# AL17150.net
KiCad netlist of a schematic drawn in Altium Designer
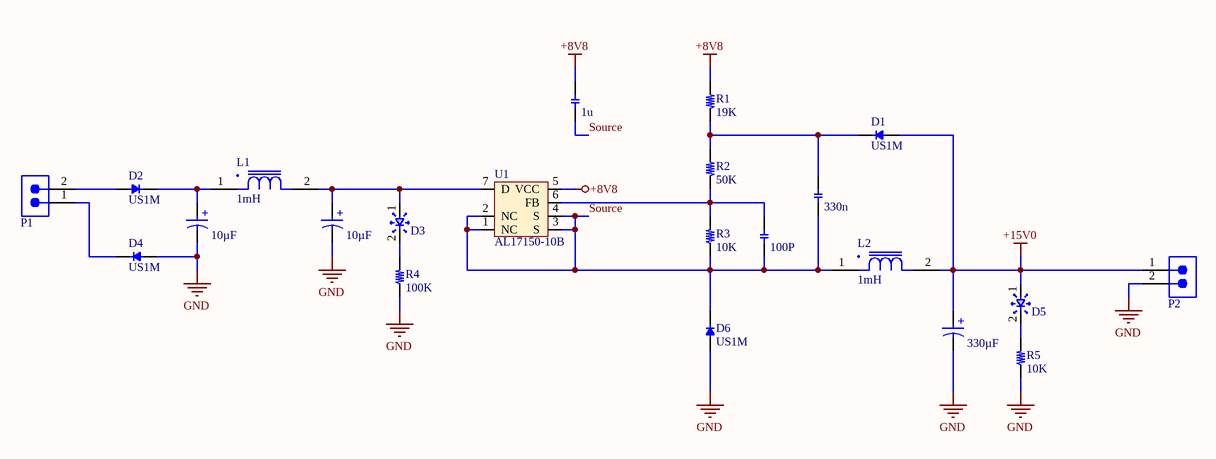
[diagram p0: AL17150.SchDoc]

(export (version "E")
  (design (tool "Eeschema 10.0.6"))
  (components
    (comp (ref "C1")
      (value "1u")
      (footprint "C 1206")
      (description "CAP_SMD")
      (libsource (lib "radmehr_library") (part "CAP_SMD"))
    )
    (comp (ref "C2")
      (value "330n")
      (footprint "C 1206")
      (description "CAP_SMD")
      (libsource (lib "radmehr_library") (part "CAP_SMD"))
    )
    (comp (ref "C3")
      (value "10µF")
      (footprint "WCAP-AT1H_D13H20")
      (description "WCAP-AT1H Aluminum Electrolytic Capacitor, Radial, THT, D13 x H20mm, 10µF, 450V")
      (fields
        (field (name "MANUFACTURER PART NUMBER") "860241478003")
        (field (name "MANUFACTURER") "Wurth Elektronik")
      )
      (libsource (lib "Altium_WCAP-AT1H (rev22c)") (part "860241478003"))
    )
    (comp (ref "C4")
      (value "10µF")
      (footprint "WCAP-AT1H_D13H20")
      (description "WCAP-AT1H Aluminum Electrolytic Capacitor, Radial, THT, D13 x H20mm, 10µF, 450V")
      (fields
        (field (name "MANUFACTURER PART NUMBER") "860241478003")
        (field (name "MANUFACTURER") "Wurth Elektronik")
      )
      (libsource (lib "Altium_WCAP-AT1H (rev22c)") (part "860241478003"))
    )
    (comp (ref "C5")
      (value "100P")
      (footprint "C 1206")
      (description "CAP_SMD")
      (libsource (lib "radmehr_library") (part "CAP_SMD"))
    )
    (comp (ref "C6")
      (value "330µF")
      (footprint "WCAP-AT1H_D13H20")
      (description "WCAP-AT1H Aluminum Electrolytic Capacitor, Radial, THT, D13 x H20mm, 330µF, 35V")
      (fields
        (field (name "MANUFACTURER PART NUMBER") "860240578009")
        (field (name "MANUFACTURER") "Wurth Elektronik")
      )
      (libsource (lib "Altium_WCAP-AT1H (rev22c)") (part "860240578009"))
    )
    (comp (ref "D1")
      (value "US1M")
      (footprint "DIOD_SMA")
      (description "DIOD_SMD")
      (libsource (lib "radmehr_library") (part "DIOD_SMD"))
    )
    (comp (ref "D2")
      (value "US1M")
      (footprint "DIOD_SMA")
      (description "DIOD_SMD")
      (libsource (lib "radmehr_library") (part "DIOD_SMD"))
    )
    (comp (ref "D3")
      (value "LED_SMD")
      (footprint "D 1206")
      (libsource (lib "radmehr_library") (part "LED_SMD"))
    )
    (comp (ref "D4")
      (value "US1M")
      (footprint "DIOD_SMA")
      (description "DIOD_SMD")
      (libsource (lib "radmehr_library") (part "DIOD_SMD"))
    )
    (comp (ref "D5")
      (value "LED_SMD")
      (footprint "D 1206")
      (libsource (lib "radmehr_library") (part "LED_SMD"))
    )
    (comp (ref "D6")
      (value "US1M")
      (footprint "DIOD_SMA")
      (description "DIOD_SMD")
      (libsource (lib "radmehr_library") (part "DIOD_SMD"))
    )
    (comp (ref "L1")
      (value "1mH")
      (footprint "L_5mm_DIP-2")
      (description "Inductor")
      (libsource (lib "radmehr_library") (part "Inductor"))
    )
    (comp (ref "L2")
      (value "1mH")
      (footprint "L_5mm_DIP-2")
      (description "Inductor")
      (libsource (lib "radmehr_library") (part "Inductor"))
    )
    (comp (ref "P1")
      (value "691322310002")
      (footprint "691322310002")
      (description "WR-TBL Series 322 Horizontal PCB Header, Through Hole, pitch 3.81mm, 2p")
      (fields (field (name "MANUFACTURER") "Wurth Elektronik"))
      (libsource (lib "Altium_WR-TBL (rev22a)") (part "691322310002"))
    )
    (comp (ref "P2")
      (value "691322310002")
      (footprint "691322310002")
      (description "WR-TBL Series 322 Horizontal PCB Header, Through Hole, pitch 3.81mm, 2p")
      (fields (field (name "MANUFACTURER") "Wurth Elektronik"))
      (libsource (lib "Altium_WR-TBL (rev22a)") (part "691322310002"))
    )
    (comp (ref "R1")
      (value "19K")
      (footprint "R 1206")
      (description "RES_SMD")
      (libsource (lib "radmehr_library") (part "RES_SMD"))
    )
    (comp (ref "R2")
      (value "50K")
      (footprint "R 1206")
      (description "RES_SMD")
      (libsource (lib "radmehr_library") (part "RES_SMD"))
    )
    (comp (ref "R3")
      (value "10K")
      (footprint "R 1206")
      (description "RES_SMD")
      (libsource (lib "radmehr_library") (part "RES_SMD"))
    )
    (comp (ref "R4")
      (value "100K")
      (footprint "R 1206")
      (description "RES_SMD")
      (libsource (lib "radmehr_library") (part "RES_SMD"))
    )
    (comp (ref "R5")
      (value "10K")
      (footprint "R 1206")
      (description "RES_SMD")
      (libsource (lib "radmehr_library") (part "RES_SMD"))
    )
    (comp (ref "U1")
      (value "AL17150-10B")
      (footprint "SOIC-7")
      (libsource (lib "radmehr_library") (part "AL17150-10B"))
    )
  )
  (nets
    (net (code "1") (name "+8V8") (class "Default")
      (node (ref "C1") (pin "2") (pinfunction "2_2") (pintype "passive"))
      (node (ref "R1") (pin "1") (pinfunction "1_1") (pintype "passive"))
      (node (ref "U1") (pin "5") (pinfunction "VCC_5") (pintype "passive"))
    )
    (net (code "2") (name "+15V0") (class "Default")
      (node (ref "C6") (pin "1") (pinfunction "P_1") (pintype "passive"))
      (node (ref "D1") (pin "1") (pinfunction "1_1") (pintype "passive"))
      (node (ref "D5") (pin "1") (pintype "passive"))
      (node (ref "L2") (pin "2") (pintype "passive"))
      (node (ref "P2") (pin "1") (pinfunction "1_1") (pintype "passive"))
    )
    (net (code "3") (name "/Source") (class "Default")
      (node (ref "C1") (pin "1") (pinfunction "1_1") (pintype "passive"))
      (node (ref "C2") (pin "1") (pinfunction "1_1") (pintype "passive"))
      (node (ref "C5") (pin "1") (pinfunction "1_1") (pintype "passive"))
      (node (ref "D6") (pin "2") (pinfunction "2_2") (pintype "passive"))
      (node (ref "L2") (pin "1") (pintype "passive"))
      (node (ref "R3") (pin "1") (pinfunction "1_1") (pintype "passive"))
      (node (ref "U1") (pin "1") (pinfunction "NC_1") (pintype "passive"))
      (node (ref "U1") (pin "2") (pinfunction "NC_2") (pintype "passive"))
      (node (ref "U1") (pin "3") (pinfunction "S_3") (pintype "passive"))
      (node (ref "U1") (pin "4") (pinfunction "S_4") (pintype "passive"))
    )
    (net (code "4") (name "GND") (class "Default")
      (node (ref "C3") (pin "2") (pinfunction "N_2") (pintype "passive"))
      (node (ref "C4") (pin "2") (pinfunction "N_2") (pintype "passive"))
      (node (ref "C6") (pin "2") (pinfunction "N_2") (pintype "passive"))
      (node (ref "D4") (pin "1") (pinfunction "1_1") (pintype "passive"))
      (node (ref "D6") (pin "1") (pinfunction "1_1") (pintype "passive"))
      (node (ref "P2") (pin "2") (pinfunction "2_2") (pintype "passive"))
      (node (ref "R4") (pin "1") (pinfunction "1_1") (pintype "passive"))
      (node (ref "R5") (pin "1") (pinfunction "1_1") (pintype "passive"))
    )
    (net (code "5") (name "Net-(C2-Pad2)") (class "Default")
      (node (ref "C2") (pin "2") (pinfunction "2_2") (pintype "passive"))
      (node (ref "D1") (pin "2") (pinfunction "2_2") (pintype "passive"))
      (node (ref "R1") (pin "2") (pinfunction "2_2") (pintype "passive"))
      (node (ref "R2") (pin "1") (pinfunction "1_1") (pintype "passive"))
    )
    (net (code "6") (name "Net-(C3-P)") (class "Default")
      (node (ref "C3") (pin "1") (pinfunction "P_1") (pintype "passive"))
      (node (ref "D2") (pin "2") (pinfunction "2_2") (pintype "passive"))
      (node (ref "L1") (pin "1") (pintype "passive"))
    )
    (net (code "7") (name "Net-(C4-P)") (class "Default")
      (node (ref "C4") (pin "1") (pinfunction "P_1") (pintype "passive"))
      (node (ref "D3") (pin "1") (pintype "passive"))
      (node (ref "L1") (pin "2") (pintype "passive"))
      (node (ref "U1") (pin "7") (pinfunction "D_7") (pintype "passive"))
    )
    (net (code "8") (name "Net-(D2-Pad1)") (class "Default")
      (node (ref "D2") (pin "1") (pinfunction "1_1") (pintype "passive"))
      (node (ref "P1") (pin "2") (pinfunction "2_2") (pintype "passive"))
    )
    (net (code "9") (name "Net-(D3-Pad2)") (class "Default")
      (node (ref "D3") (pin "2") (pintype "passive"))
      (node (ref "R4") (pin "2") (pinfunction "2_2") (pintype "passive"))
    )
    (net (code "10") (name "Net-(D4-Pad2)") (class "Default")
      (node (ref "D4") (pin "2") (pinfunction "2_2") (pintype "passive"))
      (node (ref "P1") (pin "1") (pinfunction "1_1") (pintype "passive"))
    )
    (net (code "11") (name "Net-(D5-Pad2)") (class "Default")
      (node (ref "D5") (pin "2") (pintype "passive"))
      (node (ref "R5") (pin "2") (pinfunction "2_2") (pintype "passive"))
    )
    (net (code "12") (name "Net-(U1-FB)") (class "Default")
      (node (ref "C5") (pin "2") (pinfunction "2_2") (pintype "passive"))
      (node (ref "R2") (pin "2") (pinfunction "2_2") (pintype "passive"))
      (node (ref "R3") (pin "2") (pinfunction "2_2") (pintype "passive"))
      (node (ref "U1") (pin "6") (pinfunction "FB_6") (pintype "passive"))
    )
  )
)
